# MotherboardThin.net
KiCad netlist of a schematic drawn in EAGLE
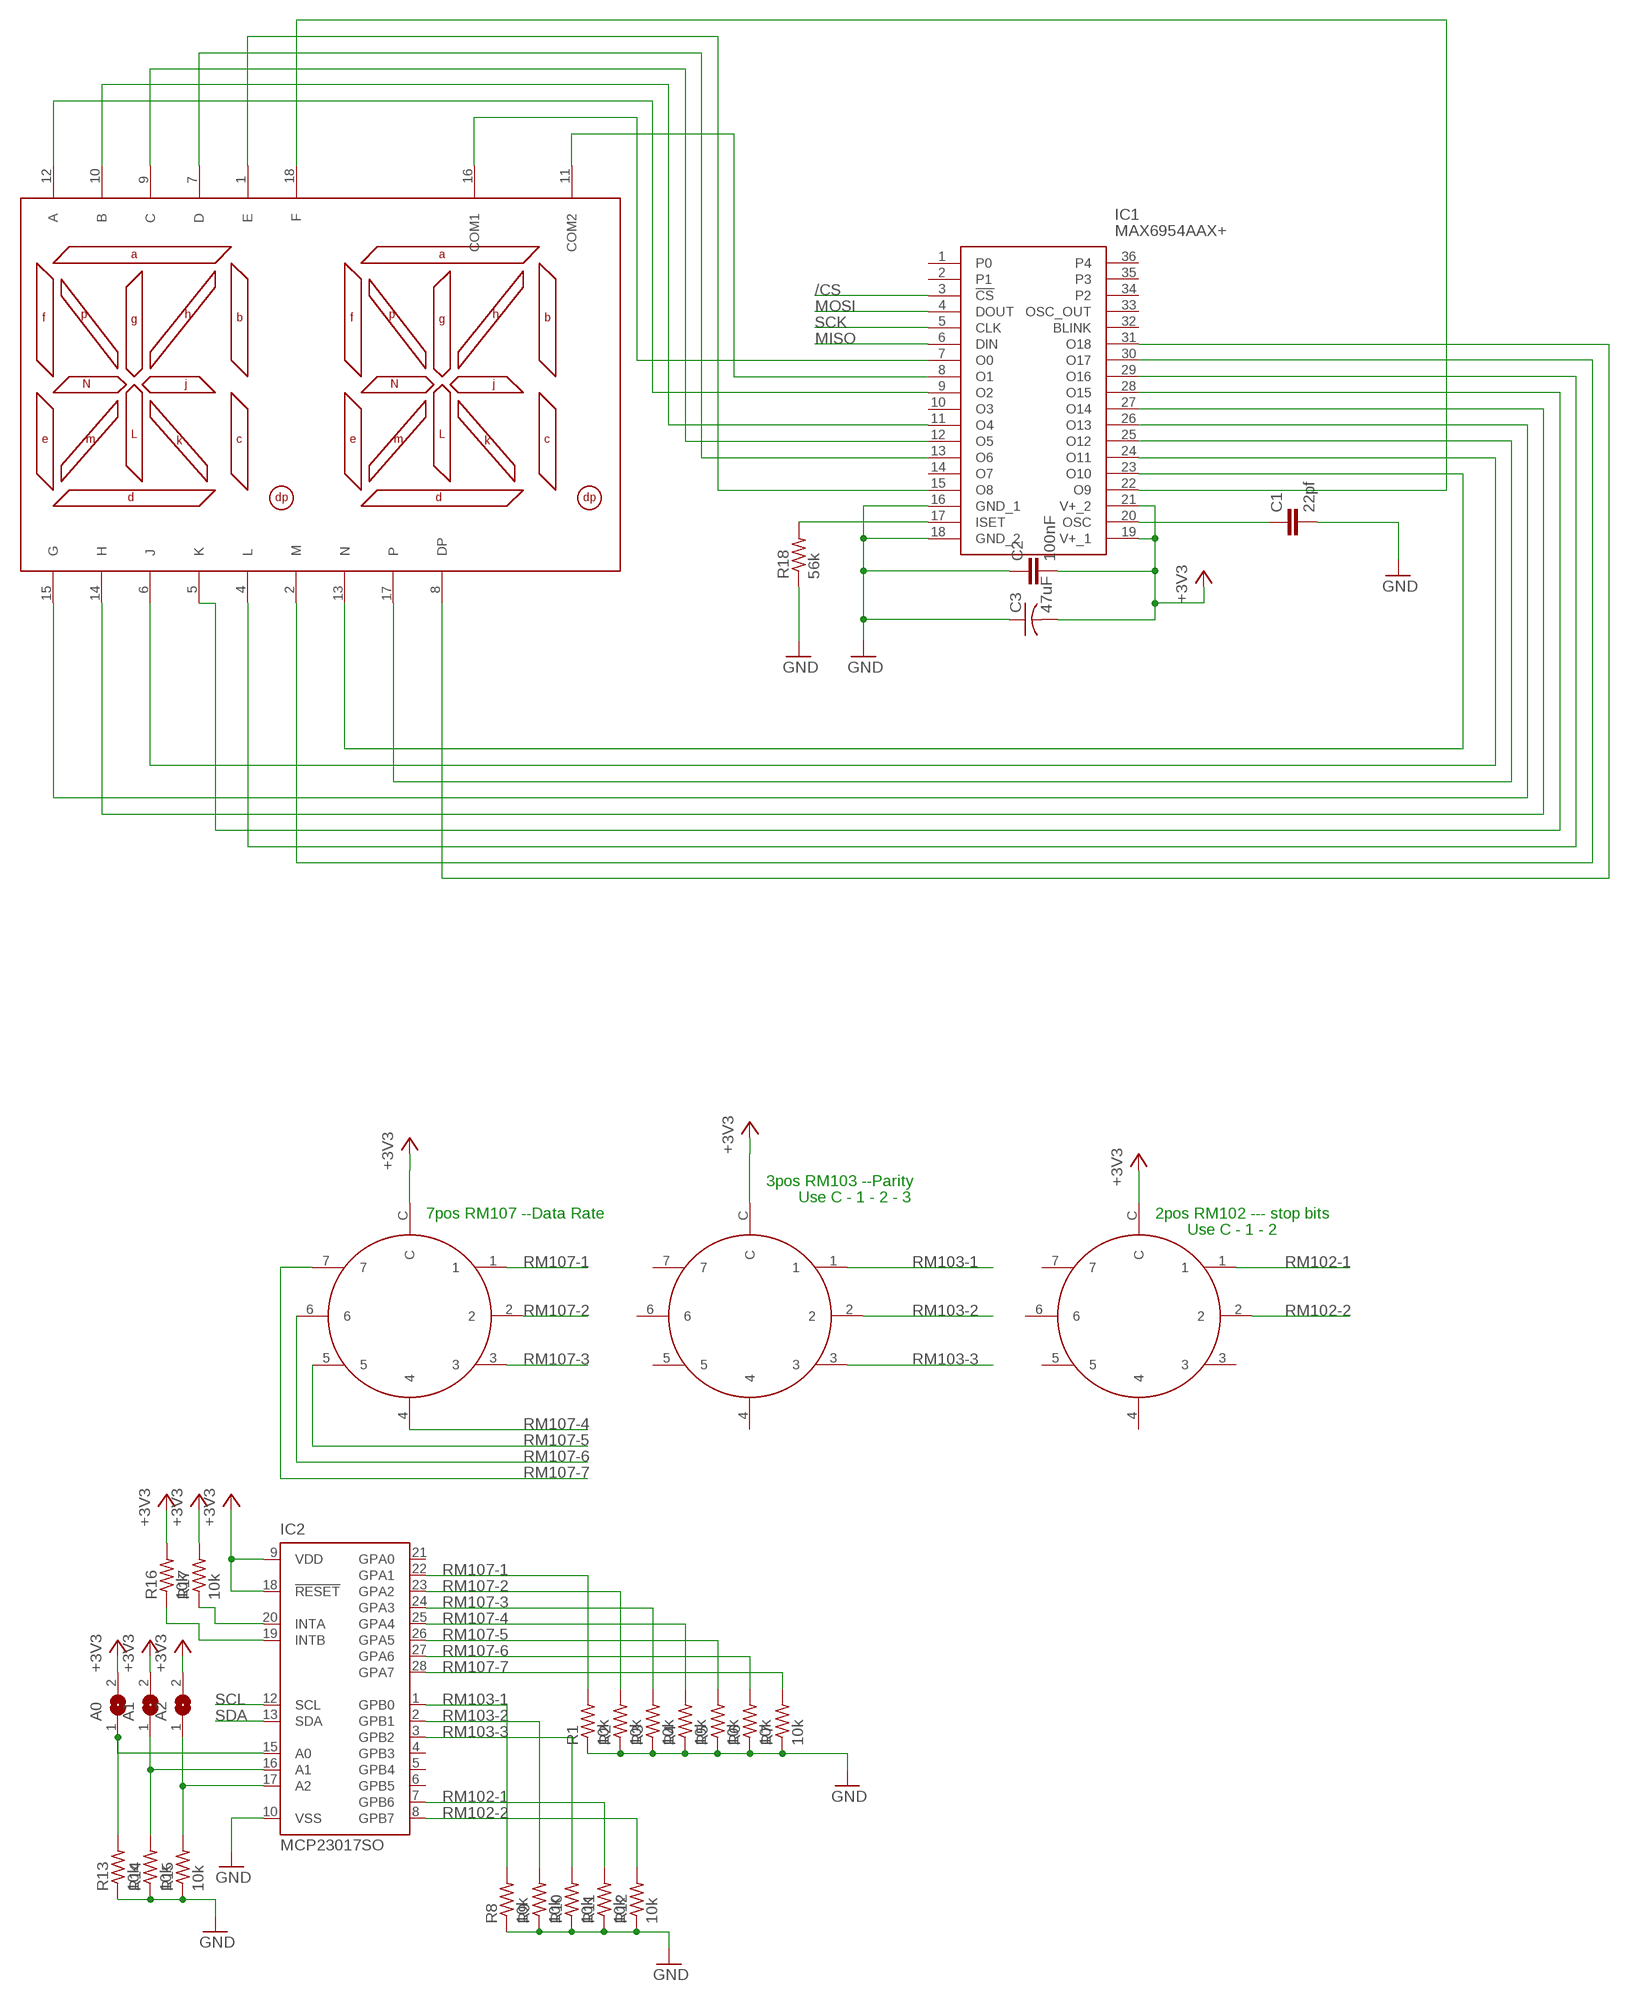
[diagram p0: schematic, sheet 1, part 1 of 2]
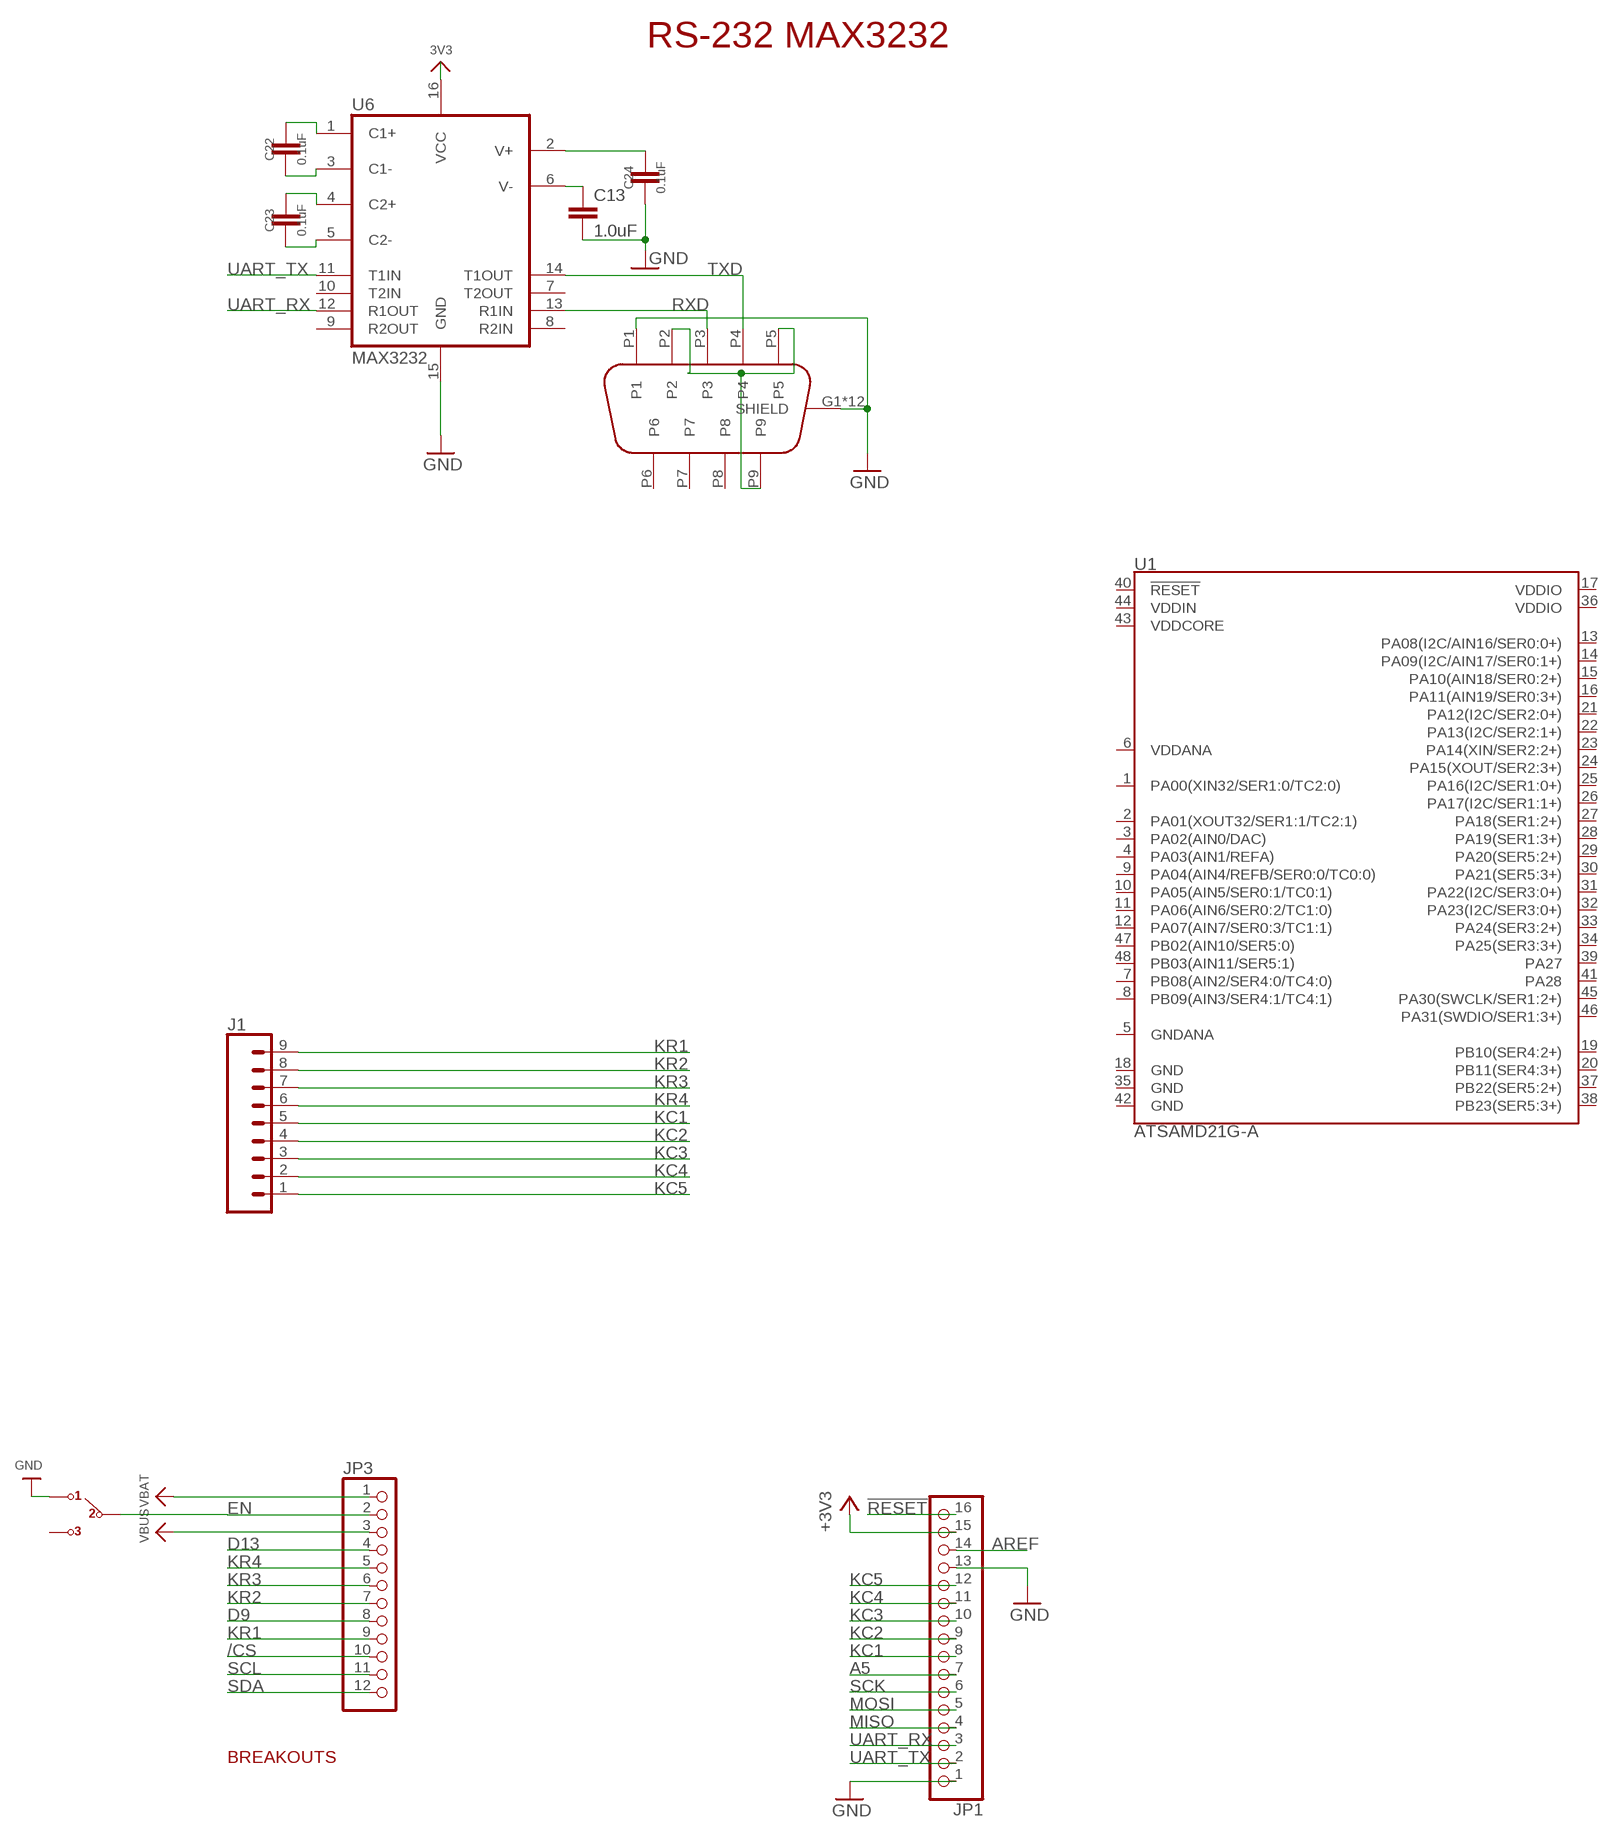
[diagram p1: schematic, sheet 1, part 2 of 2]

(export (version "E")
  (design (tool "Eeschema 10.0.6"))
  (components
    (comp (ref "A0") (value "SJ") (footprint "eagle-import:SJ") (libsource (lib "eagle-import") (part "SJ")))
    (comp (ref "A1") (value "SJ") (footprint "eagle-import:SJ") (libsource (lib "eagle-import") (part "SJ")))
    (comp (ref "A2") (value "SJ") (footprint "eagle-import:SJ") (libsource (lib "eagle-import") (part "SJ")))
    (comp (ref "C1")
      (value "22pf")
      (footprint "eagle-import:0805")
      (libsource (lib "eagle-import") (part "1.0UF-0805-25V-(+80/-20%)"))
    )
    (comp (ref "C2")
      (value "100nF")
      (footprint "eagle-import:0805")
      (libsource (lib "eagle-import") (part "1.0UF-0805-25V-(+80/-20%)"))
    )
    (comp (ref "C3")
      (value "47uF")
      (footprint "eagle-import:C1206")
      (libsource (lib "eagle-import") (part "C-USC1206"))
    )
    (comp (ref "C13")
      (value "1.0uF")
      (footprint "eagle-import:0805")
      (libsource (lib "eagle-import") (part "1.0UF-0805-25V-10%"))
    )
    (comp (ref "C22")
      (value "0.1uF")
      (footprint "eagle-import:0805")
      (libsource (lib "eagle-import") (part "1.0UF-0805-25V-10%"))
    )
    (comp (ref "C23")
      (value "0.1uF")
      (footprint "eagle-import:0805")
      (libsource (lib "eagle-import") (part "1.0UF-0805-25V-10%"))
    )
    (comp (ref "C24")
      (value "0.1uF")
      (footprint "eagle-import:0805")
      (libsource (lib "eagle-import") (part "1.0UF-0805-25V-10%"))
    )
    (comp (ref "DE9FEMALE")
      (value "EDGEMOUNTDE9")
      (footprint "eagle-import:DE09S065TLF")
      (libsource (lib "eagle-import") (part "EDGEMOUNTDE9"))
    )
    (comp (ref "IC1")
      (value "MAX6954AAX+")
      (footprint "eagle-import:SOP80P1030X264-36N")
      (fields (field (name "MOUSER_PART_NUMBER") "700-MAX6954AAX"))
      (libsource (lib "eagle-import") (part "MAX6954AAX+"))
    )
    (comp (ref "IC2")
      (value "MCP23017SO")
      (footprint "eagle-import:SO28W")
      (libsource (lib "eagle-import") (part "MCP23017SO"))
    )
    (comp (ref "J1")
      (value "CONN_09")
      (footprint "eagle-import:1X09")
      (libsource (lib "eagle-import") (part "CONN_09"))
    )
    (comp (ref "JP1")
      (value "HEADER-1X16ROUND")
      (footprint "eagle-import:1X16_ROUND")
      (libsource (lib "eagle-import") (part "HEADER-1X16ROUND"))
    )
    (comp (ref "JP3")
      (value "HEADER-1X12")
      (footprint "eagle-import:1X12_ROUND")
      (libsource (lib "eagle-import") (part "HEADER-1X12"))
    )
    (comp (ref "R1")
      (value "10k")
      (footprint "eagle-import:M0805")
      (libsource (lib "eagle-import") (part "R-US_M0805"))
    )
    (comp (ref "R2")
      (value "10k")
      (footprint "eagle-import:M0805")
      (libsource (lib "eagle-import") (part "R-US_M0805"))
    )
    (comp (ref "R3")
      (value "10k")
      (footprint "eagle-import:M0805")
      (libsource (lib "eagle-import") (part "R-US_M0805"))
    )
    (comp (ref "R4")
      (value "10k")
      (footprint "eagle-import:M0805")
      (libsource (lib "eagle-import") (part "R-US_M0805"))
    )
    (comp (ref "R5")
      (value "10k")
      (footprint "eagle-import:M0805")
      (libsource (lib "eagle-import") (part "R-US_M0805"))
    )
    (comp (ref "R6")
      (value "10k")
      (footprint "eagle-import:M0805")
      (libsource (lib "eagle-import") (part "R-US_M0805"))
    )
    (comp (ref "R7")
      (value "10k")
      (footprint "eagle-import:M0805")
      (libsource (lib "eagle-import") (part "R-US_M0805"))
    )
    (comp (ref "R8")
      (value "10k")
      (footprint "eagle-import:M0805")
      (libsource (lib "eagle-import") (part "R-US_M0805"))
    )
    (comp (ref "R9")
      (value "10k")
      (footprint "eagle-import:M0805")
      (libsource (lib "eagle-import") (part "R-US_M0805"))
    )
    (comp (ref "R10")
      (value "10k")
      (footprint "eagle-import:M0805")
      (libsource (lib "eagle-import") (part "R-US_M0805"))
    )
    (comp (ref "R11")
      (value "10k")
      (footprint "eagle-import:M0805")
      (libsource (lib "eagle-import") (part "R-US_M0805"))
    )
    (comp (ref "R12")
      (value "10k")
      (footprint "eagle-import:M0805")
      (libsource (lib "eagle-import") (part "R-US_M0805"))
    )
    (comp (ref "R13")
      (value "10k")
      (footprint "eagle-import:M0805")
      (libsource (lib "eagle-import") (part "R-US_M0805"))
    )
    (comp (ref "R14")
      (value "10k")
      (footprint "eagle-import:M0805")
      (libsource (lib "eagle-import") (part "R-US_M0805"))
    )
    (comp (ref "R15")
      (value "10k")
      (footprint "eagle-import:M0805")
      (libsource (lib "eagle-import") (part "R-US_M0805"))
    )
    (comp (ref "R16")
      (value "10k")
      (footprint "eagle-import:M0805")
      (libsource (lib "eagle-import") (part "R-US_M0805"))
    )
    (comp (ref "R17")
      (value "10k")
      (footprint "eagle-import:M0805")
      (libsource (lib "eagle-import") (part "R-US_M0805"))
    )
    (comp (ref "R18")
      (value "56k")
      (footprint "eagle-import:M0805")
      (libsource (lib "eagle-import") (part "R-US_M0805"))
    )
    (comp (ref "U$1")
      (value "HDSP-A27C")
      (footprint "eagle-import:DIP-18")
      (libsource (lib "eagle-import") (part "HDSP-A27C"))
    )
    (comp (ref "U$2")
      (value "RM107772BCB")
      (footprint "eagle-import:RM107772BCB")
      (libsource (lib "eagle-import") (part "RM107772BCB"))
    )
    (comp (ref "U$3")
      (value "RM107772BCB")
      (footprint "eagle-import:RM107772BCB")
      (libsource (lib "eagle-import") (part "RM107772BCB"))
    )
    (comp (ref "U$5")
      (value "OS102011MA1QN1")
      (footprint "eagle-import:OS102011MA1QN1")
      (libsource (lib "eagle-import") (part "OS102011MA1QN1"))
    )
    (comp (ref "U$6")
      (value "RM107772BCB")
      (footprint "eagle-import:RM107772BCB")
      (libsource (lib "eagle-import") (part "RM107772BCB"))
    )
    (comp (ref "U1")
      (value "ATSAMD21G-A")
      (footprint "eagle-import:TQFP-48")
      (libsource (lib "eagle-import") (part "ATSAMD21G-A"))
    )
    (comp (ref "U6")
      (value "MAX3232")
      (footprint "eagle-import:SO16")
      (libsource (lib "eagle-import") (part "MAX2323SOIC16"))
    )
  )
  (nets
    (net (code "1") (name "+3V3") (class "Default")
      (node (ref "A0") (pin "2") (pinfunction "2_2") (pintype "passive"))
      (node (ref "A1") (pin "2") (pinfunction "2_2") (pintype "passive"))
      (node (ref "A2") (pin "2") (pinfunction "2_2") (pintype "passive"))
      (node (ref "C2") (pin "2") (pinfunction "2_2") (pintype "passive"))
      (node (ref "C3") (pin "2") (pinfunction "2_2") (pintype "passive"))
      (node (ref "IC1") (pin "19") (pinfunction "V+_1_19") (pintype "bidirectional"))
      (node (ref "IC1") (pin "21") (pinfunction "V+_2_21") (pintype "bidirectional"))
      (node (ref "IC2") (pin "18") (pinfunction "~{RESET}_18") (pintype "input"))
      (node (ref "IC2") (pin "9") (pinfunction "VDD_9") (pintype "power_in"))
      (node (ref "JP1") (pin "15") (pinfunction "15_15") (pintype "passive"))
      (node (ref "R16") (pin "2") (pinfunction "2_2") (pintype "passive"))
      (node (ref "R17") (pin "2") (pinfunction "2_2") (pintype "passive"))
      (node (ref "U$2") (pin "C") (pinfunction "C_C") (pintype "bidirectional"))
      (node (ref "U$3") (pin "C") (pinfunction "C_C") (pintype "bidirectional"))
      (node (ref "U$6") (pin "C") (pinfunction "C_C") (pintype "bidirectional"))
    )
    (net (code "2") (name "/A5") (class "Default")
      (node (ref "JP1") (pin "7") (pinfunction "7_7") (pintype "passive"))
    )
    (net (code "3") (name "/AREF") (class "Default")
      (node (ref "JP1") (pin "14") (pinfunction "14_14") (pintype "passive"))
    )
    (net (code "4") (name "/D9") (class "Default")
      (node (ref "JP3") (pin "8") (pinfunction "8_8") (pintype "passive"))
    )
    (net (code "5") (name "/D13") (class "Default")
      (node (ref "JP3") (pin "4") (pinfunction "4_4") (pintype "passive"))
    )
    (net (code "6") (name "/EN") (class "Default")
      (node (ref "JP3") (pin "2") (pinfunction "2_2") (pintype "passive"))
      (node (ref "U$5") (pin "P$2") (pinfunction "P$2_P$2") (pintype "bidirectional"))
    )
    (net (code "7") (name "/KC1") (class "Default")
      (node (ref "J1") (pin "5") (pinfunction "5_5") (pintype "passive"))
      (node (ref "JP1") (pin "8") (pinfunction "8_8") (pintype "passive"))
    )
    (net (code "8") (name "/KC2") (class "Default")
      (node (ref "J1") (pin "4") (pinfunction "4_4") (pintype "passive"))
      (node (ref "JP1") (pin "9") (pinfunction "9_9") (pintype "passive"))
    )
    (net (code "9") (name "/KC3") (class "Default")
      (node (ref "J1") (pin "3") (pinfunction "3_3") (pintype "passive"))
      (node (ref "JP1") (pin "10") (pinfunction "10_10") (pintype "passive"))
    )
    (net (code "10") (name "/KC4") (class "Default")
      (node (ref "J1") (pin "2") (pinfunction "2_2") (pintype "passive"))
      (node (ref "JP1") (pin "11") (pinfunction "11_11") (pintype "passive"))
    )
    (net (code "11") (name "/KC5") (class "Default")
      (node (ref "J1") (pin "1") (pinfunction "1_1") (pintype "passive"))
      (node (ref "JP1") (pin "12") (pinfunction "12_12") (pintype "passive"))
    )
    (net (code "12") (name "/KR1") (class "Default")
      (node (ref "J1") (pin "9") (pinfunction "9_9") (pintype "passive"))
      (node (ref "JP3") (pin "9") (pinfunction "9_9") (pintype "passive"))
    )
    (net (code "13") (name "/KR2") (class "Default")
      (node (ref "J1") (pin "8") (pinfunction "8_8") (pintype "passive"))
      (node (ref "JP3") (pin "7") (pinfunction "7_7") (pintype "passive"))
    )
    (net (code "14") (name "/KR3") (class "Default")
      (node (ref "J1") (pin "7") (pinfunction "7_7") (pintype "passive"))
      (node (ref "JP3") (pin "6") (pinfunction "6_6") (pintype "passive"))
    )
    (net (code "15") (name "/KR4") (class "Default")
      (node (ref "J1") (pin "6") (pinfunction "6_6") (pintype "passive"))
      (node (ref "JP3") (pin "5") (pinfunction "5_5") (pintype "passive"))
    )
    (net (code "16") (name "/MISO") (class "Default")
      (node (ref "IC1") (pin "6") (pinfunction "DIN_6") (pintype "input"))
      (node (ref "JP1") (pin "4") (pinfunction "4_4") (pintype "passive"))
    )
    (net (code "17") (name "/MOSI") (class "Default")
      (node (ref "IC1") (pin "4") (pinfunction "DOUT_4") (pintype "output"))
      (node (ref "JP1") (pin "5") (pinfunction "5_5") (pintype "passive"))
    )
    (net (code "18") (name "/RM102-1") (class "Default")
      (node (ref "IC2") (pin "7") (pinfunction "GPB6_7") (pintype "bidirectional"))
      (node (ref "R11") (pin "2") (pinfunction "2_2") (pintype "passive"))
      (node (ref "U$6") (pin "1") (pinfunction "1_1") (pintype "bidirectional"))
    )
    (net (code "19") (name "/RM102-2") (class "Default")
      (node (ref "IC2") (pin "8") (pinfunction "GPB7_8") (pintype "bidirectional"))
      (node (ref "R12") (pin "2") (pinfunction "2_2") (pintype "passive"))
      (node (ref "U$6") (pin "2") (pinfunction "2_2") (pintype "bidirectional"))
    )
    (net (code "20") (name "/RM103-1") (class "Default")
      (node (ref "IC2") (pin "1") (pinfunction "GPB0_1") (pintype "bidirectional"))
      (node (ref "R8") (pin "2") (pinfunction "2_2") (pintype "passive"))
      (node (ref "U$3") (pin "1") (pinfunction "1_1") (pintype "bidirectional"))
    )
    (net (code "21") (name "/RM103-2") (class "Default")
      (node (ref "IC2") (pin "2") (pinfunction "GPB1_2") (pintype "bidirectional"))
      (node (ref "R9") (pin "2") (pinfunction "2_2") (pintype "passive"))
      (node (ref "U$3") (pin "2") (pinfunction "2_2") (pintype "bidirectional"))
    )
    (net (code "22") (name "/RM103-3") (class "Default")
      (node (ref "IC2") (pin "3") (pinfunction "GPB2_3") (pintype "bidirectional"))
      (node (ref "R10") (pin "2") (pinfunction "2_2") (pintype "passive"))
      (node (ref "U$3") (pin "3") (pinfunction "3_3") (pintype "bidirectional"))
    )
    (net (code "23") (name "/RM107-1") (class "Default")
      (node (ref "IC2") (pin "22") (pinfunction "GPA1_22") (pintype "bidirectional"))
      (node (ref "R1") (pin "2") (pinfunction "2_2") (pintype "passive"))
      (node (ref "U$2") (pin "1") (pinfunction "1_1") (pintype "bidirectional"))
    )
    (net (code "24") (name "/RM107-2") (class "Default")
      (node (ref "IC2") (pin "23") (pinfunction "GPA2_23") (pintype "bidirectional"))
      (node (ref "R2") (pin "2") (pinfunction "2_2") (pintype "passive"))
      (node (ref "U$2") (pin "2") (pinfunction "2_2") (pintype "bidirectional"))
    )
    (net (code "25") (name "/RM107-3") (class "Default")
      (node (ref "IC2") (pin "24") (pinfunction "GPA3_24") (pintype "bidirectional"))
      (node (ref "R3") (pin "2") (pinfunction "2_2") (pintype "passive"))
      (node (ref "U$2") (pin "3") (pinfunction "3_3") (pintype "bidirectional"))
    )
    (net (code "26") (name "/RM107-4") (class "Default")
      (node (ref "IC2") (pin "25") (pinfunction "GPA4_25") (pintype "bidirectional"))
      (node (ref "R4") (pin "2") (pinfunction "2_2") (pintype "passive"))
      (node (ref "U$2") (pin "4") (pinfunction "4_4") (pintype "bidirectional"))
    )
    (net (code "27") (name "/RM107-5") (class "Default")
      (node (ref "IC2") (pin "26") (pinfunction "GPA5_26") (pintype "bidirectional"))
      (node (ref "R5") (pin "2") (pinfunction "2_2") (pintype "passive"))
      (node (ref "U$2") (pin "5") (pinfunction "5_5") (pintype "bidirectional"))
    )
    (net (code "28") (name "/RM107-6") (class "Default")
      (node (ref "IC2") (pin "27") (pinfunction "GPA6_27") (pintype "bidirectional"))
      (node (ref "R6") (pin "2") (pinfunction "2_2") (pintype "passive"))
      (node (ref "U$2") (pin "6") (pinfunction "6_6") (pintype "bidirectional"))
    )
    (net (code "29") (name "/RM107-7") (class "Default")
      (node (ref "IC2") (pin "28") (pinfunction "GPA7_28") (pintype "bidirectional"))
      (node (ref "R7") (pin "2") (pinfunction "2_2") (pintype "passive"))
      (node (ref "U$2") (pin "7") (pinfunction "7_7") (pintype "bidirectional"))
    )
    (net (code "30") (name "/RXD") (class "Default")
      (node (ref "DE9FEMALE") (pin "P3") (pinfunction "P3_P3") (pintype "bidirectional"))
      (node (ref "U6") (pin "13") (pinfunction "R1IN_13") (pintype "input"))
    )
    (net (code "31") (name "/SCK") (class "Default")
      (node (ref "IC1") (pin "5") (pinfunction "CLK_5") (pintype "input"))
      (node (ref "JP1") (pin "6") (pinfunction "6_6") (pintype "passive"))
    )
    (net (code "32") (name "/SCL") (class "Default")
      (node (ref "IC2") (pin "12") (pinfunction "SCL_12") (pintype "input"))
      (node (ref "JP3") (pin "11") (pinfunction "11_11") (pintype "passive"))
    )
    (net (code "33") (name "/SDA") (class "Default")
      (node (ref "IC2") (pin "13") (pinfunction "SDA_13") (pintype "bidirectional"))
      (node (ref "JP3") (pin "12") (pinfunction "12_12") (pintype "passive"))
    )
    (net (code "34") (name "/TXD") (class "Default")
      (node (ref "DE9FEMALE") (pin "P4") (pinfunction "P4_P4") (pintype "bidirectional"))
      (node (ref "U6") (pin "14") (pinfunction "T1OUT_14") (pintype "output"))
    )
    (net (code "35") (name "/UART_RX") (class "Default")
      (node (ref "JP1") (pin "3") (pinfunction "3_3") (pintype "passive"))
      (node (ref "U6") (pin "12") (pinfunction "R1OUT_12") (pintype "output"))
    )
    (net (code "36") (name "/UART_TX") (class "Default")
      (node (ref "JP1") (pin "2") (pinfunction "2_2") (pintype "passive"))
      (node (ref "U6") (pin "11") (pinfunction "T1IN_11") (pintype "input"))
    )
    (net (code "37") (name "/{slash}CS") (class "Default")
      (node (ref "IC1") (pin "3") (pinfunction "~{CS}_3") (pintype "input"))
      (node (ref "JP3") (pin "10") (pinfunction "10_10") (pintype "passive"))
    )
    (net (code "38") (name "/~{RESET}") (class "Default")
      (node (ref "JP1") (pin "16") (pinfunction "16_16") (pintype "passive"))
    )
    (net (code "39") (name "3V3") (class "Default")
      (node (ref "U6") (pin "16") (pinfunction "VCC_16") (pintype "bidirectional"))
    )
    (net (code "40") (name "GND") (class "Default")
      (node (ref "C1") (pin "2") (pinfunction "2_2") (pintype "passive"))
      (node (ref "C13") (pin "2") (pinfunction "2_2") (pintype "passive"))
      (node (ref "C2") (pin "1") (pinfunction "1_1") (pintype "passive"))
      (node (ref "C24") (pin "2") (pinfunction "2_2") (pintype "passive"))
      (node (ref "C3") (pin "1") (pinfunction "1_1") (pintype "passive"))
      (node (ref "DE9FEMALE") (pin "G1") (pinfunction "SHIELD_G1") (pintype "bidirectional"))
      (node (ref "DE9FEMALE") (pin "G10") (pinfunction "SHIELD_G10") (pintype "bidirectional"))
      (node (ref "DE9FEMALE") (pin "G11") (pinfunction "SHIELD_G11") (pintype "bidirectional"))
      (node (ref "DE9FEMALE") (pin "G12") (pinfunction "SHIELD_G12") (pintype "bidirectional"))
      (node (ref "DE9FEMALE") (pin "G2") (pinfunction "SHIELD_G2") (pintype "bidirectional"))
      (node (ref "DE9FEMALE") (pin "G3") (pinfunction "SHIELD_G3") (pintype "bidirectional"))
      (node (ref "DE9FEMALE") (pin "G4") (pinfunction "SHIELD_G4") (pintype "bidirectional"))
      (node (ref "DE9FEMALE") (pin "G5") (pinfunction "SHIELD_G5") (pintype "bidirectional"))
      (node (ref "DE9FEMALE") (pin "G6") (pinfunction "SHIELD_G6") (pintype "bidirectional"))
      (node (ref "DE9FEMALE") (pin "G7") (pinfunction "SHIELD_G7") (pintype "bidirectional"))
      (node (ref "DE9FEMALE") (pin "G8") (pinfunction "SHIELD_G8") (pintype "bidirectional"))
      (node (ref "DE9FEMALE") (pin "G9") (pinfunction "SHIELD_G9") (pintype "bidirectional"))
      (node (ref "DE9FEMALE") (pin "P1") (pinfunction "P1_P1") (pintype "bidirectional"))
      (node (ref "IC1") (pin "16") (pinfunction "GND_1_16") (pintype "power_in"))
      (node (ref "IC1") (pin "18") (pinfunction "GND_2_18") (pintype "power_in"))
      (node (ref "IC2") (pin "10") (pinfunction "VSS_10") (pintype "power_in"))
      (node (ref "JP1") (pin "1") (pinfunction "1_1") (pintype "passive"))
      (node (ref "JP1") (pin "13") (pinfunction "13_13") (pintype "passive"))
      (node (ref "R1") (pin "1") (pinfunction "1_1") (pintype "passive"))
      (node (ref "R10") (pin "1") (pinfunction "1_1") (pintype "passive"))
      (node (ref "R11") (pin "1") (pinfunction "1_1") (pintype "passive"))
      (node (ref "R12") (pin "1") (pinfunction "1_1") (pintype "passive"))
      (node (ref "R13") (pin "1") (pinfunction "1_1") (pintype "passive"))
      (node (ref "R14") (pin "1") (pinfunction "1_1") (pintype "passive"))
      (node (ref "R15") (pin "1") (pinfunction "1_1") (pintype "passive"))
      (node (ref "R18") (pin "1") (pinfunction "1_1") (pintype "passive"))
      (node (ref "R2") (pin "1") (pinfunction "1_1") (pintype "passive"))
      (node (ref "R3") (pin "1") (pinfunction "1_1") (pintype "passive"))
      (node (ref "R4") (pin "1") (pinfunction "1_1") (pintype "passive"))
      (node (ref "R5") (pin "1") (pinfunction "1_1") (pintype "passive"))
      (node (ref "R6") (pin "1") (pinfunction "1_1") (pintype "passive"))
      (node (ref "R7") (pin "1") (pinfunction "1_1") (pintype "passive"))
      (node (ref "R8") (pin "1") (pinfunction "1_1") (pintype "passive"))
      (node (ref "R9") (pin "1") (pinfunction "1_1") (pintype "passive"))
      (node (ref "U$5") (pin "P$1") (pinfunction "P$1_P$1") (pintype "bidirectional"))
      (node (ref "U6") (pin "15") (pinfunction "GND_15") (pintype "bidirectional"))
    )
    (net (code "41") (name "Net-(DE9FEMALE-PadP2)") (class "Default")
      (node (ref "DE9FEMALE") (pin "P2") (pinfunction "P2_P2") (pintype "bidirectional"))
      (node (ref "DE9FEMALE") (pin "P5") (pinfunction "P5_P5") (pintype "bidirectional"))
      (node (ref "DE9FEMALE") (pin "P9") (pinfunction "P9_P9") (pintype "bidirectional"))
    )
    (net (code "42") (name "Net-(IC1-ISET)") (class "Default")
      (node (ref "IC1") (pin "17") (pinfunction "ISET_17") (pintype "bidirectional"))
      (node (ref "R18") (pin "2") (pinfunction "2_2") (pintype "passive"))
    )
    (net (code "43") (name "Net-(IC1-O0)") (class "Default")
      (node (ref "IC1") (pin "7") (pinfunction "O0_7") (pintype "output"))
      (node (ref "U$1") (pin "16") (pinfunction "COM1_16") (pintype "bidirectional"))
    )
    (net (code "44") (name "Net-(IC1-O1)") (class "Default")
      (node (ref "IC1") (pin "8") (pinfunction "O1_8") (pintype "output"))
      (node (ref "U$1") (pin "11") (pinfunction "COM2_11") (pintype "bidirectional"))
    )
    (net (code "45") (name "Net-(IC1-O2)") (class "Default")
      (node (ref "IC1") (pin "9") (pinfunction "O2_9") (pintype "output"))
      (node (ref "U$1") (pin "12") (pinfunction "A_12") (pintype "bidirectional"))
    )
    (net (code "46") (name "Net-(IC1-O4)") (class "Default")
      (node (ref "IC1") (pin "11") (pinfunction "O4_11") (pintype "output"))
      (node (ref "U$1") (pin "10") (pinfunction "B_10") (pintype "bidirectional"))
    )
    (net (code "47") (name "Net-(IC1-O5)") (class "Default")
      (node (ref "IC1") (pin "12") (pinfunction "O5_12") (pintype "output"))
      (node (ref "U$1") (pin "9") (pinfunction "C_9") (pintype "bidirectional"))
    )
    (net (code "48") (name "Net-(IC1-O6)") (class "Default")
      (node (ref "IC1") (pin "13") (pinfunction "O6_13") (pintype "output"))
      (node (ref "U$1") (pin "7") (pinfunction "D_7") (pintype "bidirectional"))
    )
    (net (code "49") (name "Net-(IC1-O8)") (class "Default")
      (node (ref "IC1") (pin "15") (pinfunction "O8_15") (pintype "output"))
      (node (ref "U$1") (pin "1") (pinfunction "E_1") (pintype "bidirectional"))
    )
    (net (code "50") (name "Net-(IC1-O9)") (class "Default")
      (node (ref "IC1") (pin "22") (pinfunction "O9_22") (pintype "bidirectional"))
      (node (ref "U$1") (pin "18") (pinfunction "F_18") (pintype "bidirectional"))
    )
    (net (code "51") (name "Net-(IC1-O10)") (class "Default")
      (node (ref "IC1") (pin "23") (pinfunction "O10_23") (pintype "bidirectional"))
      (node (ref "U$1") (pin "13") (pinfunction "N_13") (pintype "bidirectional"))
    )
    (net (code "52") (name "Net-(IC1-O11)") (class "Default")
      (node (ref "IC1") (pin "24") (pinfunction "O11_24") (pintype "bidirectional"))
      (node (ref "U$1") (pin "6") (pinfunction "J_6") (pintype "bidirectional"))
    )
    (net (code "53") (name "Net-(IC1-O12)") (class "Default")
      (node (ref "IC1") (pin "25") (pinfunction "O12_25") (pintype "bidirectional"))
      (node (ref "U$1") (pin "17") (pinfunction "P_17") (pintype "bidirectional"))
    )
    (net (code "54") (name "Net-(IC1-O13)") (class "Default")
      (node (ref "IC1") (pin "26") (pinfunction "O13_26") (pintype "bidirectional"))
      (node (ref "U$1") (pin "15") (pinfunction "G_15") (pintype "bidirectional"))
    )
    (net (code "55") (name "Net-(IC1-O14)") (class "Default")
      (node (ref "IC1") (pin "27") (pinfunction "O14_27") (pintype "bidirectional"))
      (node (ref "U$1") (pin "14") (pinfunction "H_14") (pintype "bidirectional"))
    )
    (net (code "56") (name "Net-(IC1-O15)") (class "Default")
      (node (ref "IC1") (pin "28") (pinfunction "O15_28") (pintype "bidirectional"))
      (node (ref "U$1") (pin "5") (pinfunction "K_5") (pintype "bidirectional"))
    )
    (net (code "57") (name "Net-(IC1-O16)") (class "Default")
      (node (ref "IC1") (pin "29") (pinfunction "O16_29") (pintype "bidirectional"))
      (node (ref "U$1") (pin "4") (pinfunction "L_4") (pintype "bidirectional"))
    )
    (net (code "58") (name "Net-(IC1-O17)") (class "Default")
      (node (ref "IC1") (pin "30") (pinfunction "O17_30") (pintype "bidirectional"))
      (node (ref "U$1") (pin "2") (pinfunction "M_2") (pintype "bidirectional"))
    )
    (net (code "59") (name "Net-(IC1-O18)") (class "Default")
      (node (ref "IC1") (pin "31") (pinfunction "O18_31") (pintype "bidirectional"))
      (node (ref "U$1") (pin "8") (pinfunction "DP_8") (pintype "bidirectional"))
    )
    (net (code "60") (name "Net-(IC1-OSC)") (class "Default")
      (node (ref "C1") (pin "1") (pinfunction "1_1") (pintype "passive"))
      (node (ref "IC1") (pin "20") (pinfunction "OSC_20") (pintype "bidirectional"))
    )
    (net (code "61") (name "Net-(IC2-A0)") (class "Default")
      (node (ref "A0") (pin "1") (pinfunction "1_1") (pintype "passive"))
      (node (ref "IC2") (pin "15") (pinfunction "A0_15") (pintype "input"))
      (node (ref "R13") (pin "2") (pinfunction "2_2") (pintype "passive"))
    )
    (net (code "62") (name "Net-(IC2-A1)") (class "Default")
      (node (ref "A1") (pin "1") (pinfunction "1_1") (pintype "passive"))
      (node (ref "IC2") (pin "16") (pinfunction "A1_16") (pintype "input"))
      (node (ref "R14") (pin "2") (pinfunction "2_2") (pintype "passive"))
    )
    (net (code "63") (name "Net-(IC2-A2)") (class "Default")
      (node (ref "A2") (pin "1") (pinfunction "1_1") (pintype "passive"))
      (node (ref "IC2") (pin "17") (pinfunction "A2_17") (pintype "input"))
      (node (ref "R15") (pin "2") (pinfunction "2_2") (pintype "passive"))
    )
    (net (code "64") (name "Net-(IC2-INTA)") (class "Default")
      (node (ref "IC2") (pin "20") (pinfunction "INTA_20") (pintype "output"))
      (node (ref "R17") (pin "1") (pinfunction "1_1") (pintype "passive"))
    )
    (net (code "65") (name "Net-(IC2-INTB)") (class "Default")
      (node (ref "IC2") (pin "19") (pinfunction "INTB_19") (pintype "output"))
      (node (ref "R16") (pin "1") (pinfunction "1_1") (pintype "passive"))
    )
    (net (code "66") (name "Net-(U6-C1+)") (class "Default")
      (node (ref "C22") (pin "1") (pinfunction "1_1") (pintype "passive"))
      (node (ref "U6") (pin "1") (pinfunction "C1+_1") (pintype "bidirectional"))
    )
    (net (code "67") (name "Net-(U6-C1-)") (class "Default")
      (node (ref "C22") (pin "2") (pinfunction "2_2") (pintype "passive"))
      (node (ref "U6") (pin "3") (pinfunction "C1-_3") (pintype "bidirectional"))
    )
    (net (code "68") (name "Net-(U6-C2+)") (class "Default")
      (node (ref "C23") (pin "1") (pinfunction "1_1") (pintype "passive"))
      (node (ref "U6") (pin "4") (pinfunction "C2+_4") (pintype "bidirectional"))
    )
    (net (code "69") (name "Net-(U6-C2-)") (class "Default")
      (node (ref "C23") (pin "2") (pinfunction "2_2") (pintype "passive"))
      (node (ref "U6") (pin "5") (pinfunction "C2-_5") (pintype "bidirectional"))
    )
    (net (code "70") (name "Net-(U6-V+)") (class "Default")
      (node (ref "C24") (pin "1") (pinfunction "1_1") (pintype "passive"))
      (node (ref "U6") (pin "2") (pinfunction "V+_2") (pintype "bidirectional"))
    )
    (net (code "71") (name "Net-(U6-V-)") (class "Default")
      (node (ref "C13") (pin "1") (pinfunction "1_1") (pintype "passive"))
      (node (ref "U6") (pin "6") (pinfunction "V-_6") (pintype "bidirectional"))
    )
    (net (code "72") (name "VBAT") (class "Default")
      (node (ref "JP3") (pin "1") (pinfunction "1_1") (pintype "passive"))
    )
    (net (code "73") (name "VBUS") (class "Default")
      (node (ref "JP3") (pin "3") (pinfunction "3_3") (pintype "passive"))
    )
    (net (code "74") (name "unconnected-(DE9FEMALE-PadP6)") (class "Default")
      (node (ref "DE9FEMALE") (pin "P6") (pinfunction "P6_P6") (pintype "bidirectional"))
    )
    (net (code "75") (name "unconnected-(DE9FEMALE-PadP7)") (class "Default")
      (node (ref "DE9FEMALE") (pin "P7") (pinfunction "P7_P7") (pintype "bidirectional"))
    )
    (net (code "76") (name "unconnected-(DE9FEMALE-PadP8)") (class "Default")
      (node (ref "DE9FEMALE") (pin "P8") (pinfunction "P8_P8") (pintype "bidirectional"))
    )
    (net (code "77") (name "unconnected-(IC1-BLINK-Pad32)") (class "Default")
      (node (ref "IC1") (pin "32") (pinfunction "BLINK_32") (pintype "input"))
    )
    (net (code "78") (name "unconnected-(IC1-O3-Pad10)") (class "Default")
      (node (ref "IC1") (pin "10") (pinfunction "O3_10") (pintype "output"))
    )
    (net (code "79") (name "unconnected-(IC1-O7-Pad14)") (class "Default")
      (node (ref "IC1") (pin "14") (pinfunction "O7_14") (pintype "output"))
    )
    (net (code "80") (name "unconnected-(IC1-OSC_OUT-Pad33)") (class "Default")
      (node (ref "IC1") (pin "33") (pinfunction "OSC_OUT_33") (pintype "output"))
    )
    (net (code "81") (name "unconnected-(IC1-P0-Pad1)") (class "Default")
      (node (ref "IC1") (pin "1") (pinfunction "P0_1") (pintype "bidirectional"))
    )
    (net (code "82") (name "unconnected-(IC1-P1-Pad2)") (class "Default")
      (node (ref "IC1") (pin "2") (pinfunction "P1_2") (pintype "bidirectional"))
    )
    (net (code "83") (name "unconnected-(IC1-P2-Pad34)") (class "Default")
      (node (ref "IC1") (pin "34") (pinfunction "P2_34") (pintype "bidirectional"))
    )
    (net (code "84") (name "unconnected-(IC1-P3-Pad35)") (class "Default")
      (node (ref "IC1") (pin "35") (pinfunction "P3_35") (pintype "bidirectional"))
    )
    (net (code "85") (name "unconnected-(IC1-P4-Pad36)") (class "Default")
      (node (ref "IC1") (pin "36") (pinfunction "P4_36") (pintype "bidirectional"))
    )
    (net (code "86") (name "unconnected-(IC2-GPA0-Pad21)") (class "Default")
      (node (ref "IC2") (pin "21") (pinfunction "GPA0_21") (pintype "bidirectional"))
    )
    (net (code "87") (name "unconnected-(IC2-GPB3-Pad4)") (class "Default")
      (node (ref "IC2") (pin "4") (pinfunction "GPB3_4") (pintype "bidirectional"))
    )
    (net (code "88") (name "unconnected-(IC2-GPB4-Pad5)") (class "Default")
      (node (ref "IC2") (pin "5") (pinfunction "GPB4_5") (pintype "bidirectional"))
    )
    (net (code "89") (name "unconnected-(IC2-GPB5-Pad6)") (class "Default")
      (node (ref "IC2") (pin "6") (pinfunction "GPB5_6") (pintype "bidirectional"))
    )
    (net (code "90") (name "unconnected-(U$3-Pad4)") (class "Default")
      (node (ref "U$3") (pin "4") (pinfunction "4_4") (pintype "bidirectional"))
    )
    (net (code "91") (name "unconnected-(U$3-Pad5)") (class "Default")
      (node (ref "U$3") (pin "5") (pinfunction "5_5") (pintype "bidirectional"))
    )
    (net (code "92") (name "unconnected-(U$3-Pad6)") (class "Default")
      (node (ref "U$3") (pin "6") (pinfunction "6_6") (pintype "bidirectional"))
    )
    (net (code "93") (name "unconnected-(U$3-Pad7)") (class "Default")
      (node (ref "U$3") (pin "7") (pinfunction "7_7") (pintype "bidirectional"))
    )
    (net (code "94") (name "unconnected-(U$5-CASE-PadCASE1)") (class "Default")
      (node (ref "U$5") (pin "CASE1") (pinfunction "CASE_CASE1") (pintype "no_connect"))
    )
    (net (code "95") (name "unconnected-(U$5-CASE-PadCASE2)") (class "Default")
      (node (ref "U$5") (pin "CASE2") (pinfunction "CASE_CASE2") (pintype "no_connect"))
    )
    (net (code "96") (name "unconnected-(U$5-PadP$3)") (class "Default")
      (node (ref "U$5") (pin "P$3") (pinfunction "P$3_P$3") (pintype "bidirectional"))
    )
    (net (code "97") (name "unconnected-(U$6-Pad3)") (class "Default")
      (node (ref "U$6") (pin "3") (pinfunction "3_3") (pintype "bidirectional"))
    )
    (net (code "98") (name "unconnected-(U$6-Pad4)") (class "Default")
      (node (ref "U$6") (pin "4") (pinfunction "4_4") (pintype "bidirectional"))
    )
    (net (code "99") (name "unconnected-(U$6-Pad5)") (class "Default")
      (node (ref "U$6") (pin "5") (pinfunction "5_5") (pintype "bidirectional"))
    )
    (net (code "100") (name "unconnected-(U$6-Pad6)") (class "Default")
      (node (ref "U$6") (pin "6") (pinfunction "6_6") (pintype "bidirectional"))
    )
    (net (code "101") (name "unconnected-(U$6-Pad7)") (class "Default")
      (node (ref "U$6") (pin "7") (pinfunction "7_7") (pintype "bidirectional"))
    )
    (net (code "102") (name "unconnected-(U1-GND-Pad18)") (class "Default")
      (node (ref "U1") (pin "18") (pinfunction "GND_18") (pintype "bidirectional"))
    )
    (net (code "103") (name "unconnected-(U1-GND-Pad35)") (class "Default")
      (node (ref "U1") (pin "35") (pinfunction "GND_35") (pintype "bidirectional"))
    )
    (net (code "104") (name "unconnected-(U1-GND-Pad42)") (class "Default")
      (node (ref "U1") (pin "42") (pinfunction "GND_42") (pintype "bidirectional"))
    )
    (net (code "105") (name "unconnected-(U1-GNDANA-Pad5)") (class "Default")
      (node (ref "U1") (pin "5") (pinfunction "GNDANA_5") (pintype "bidirectional"))
    )
    (net (code "106") (name "unconnected-(U1-PA00(XIN32{slash}SER1:0{slash}TC2:0)-Pad1)") (class "Default")
      (node (ref "U1") (pin "1") (pinfunction "PA00(XIN32/SER1:0/TC2:0)_1") (pintype "bidirectional"))
    )
    (net (code "107") (name "unconnected-(U1-PA01(XOUT32{slash}SER1:1{slash}TC2:1)-Pad2)") (class "Default")
      (node (ref "U1") (pin "2") (pinfunction "PA01(XOUT32/SER1:1/TC2:1)_2") (pintype "bidirectional"))
    )
    (net (code "108") (name "unconnected-(U1-PA02(AIN0{slash}DAC)-Pad3)") (class "Default")
      (node (ref "U1") (pin "3") (pinfunction "PA02(AIN0/DAC)_3") (pintype "bidirectional"))
    )
    (net (code "109") (name "unconnected-(U1-PA03(AIN1{slash}REFA)-Pad4)") (class "Default")
      (node (ref "U1") (pin "4") (pinfunction "PA03(AIN1/REFA)_4") (pintype "bidirectional"))
    )
    (net (code "110") (name "unconnected-(U1-PA04(AIN4{slash}REFB{slash}SER0:0{slash}TC0:0)-Pad9)") (class "Default")
      (node (ref "U1") (pin "9") (pinfunction "PA04(AIN4/REFB/SER0:0/TC0:0)_9") (pintype "bidirectional"))
    )
    (net (code "111") (name "unconnected-(U1-PA05(AIN5{slash}SER0:1{slash}TC0:1)-Pad10)") (class "Default")
      (node (ref "U1") (pin "10") (pinfunction "PA05(AIN5/SER0:1/TC0:1)_10") (pintype "bidirectional"))
    )
    (net (code "112") (name "unconnected-(U1-PA06(AIN6{slash}SER0:2{slash}TC1:0)-Pad11)") (class "Default")
      (node (ref "U1") (pin "11") (pinfunction "PA06(AIN6/SER0:2/TC1:0)_11") (pintype "bidirectional"))
    )
    (net (code "113") (name "unconnected-(U1-PA07(AIN7{slash}SER0:3{slash}TC1:1)-Pad12)") (class "Default")
      (node (ref "U1") (pin "12") (pinfunction "PA07(AIN7/SER0:3/TC1:1)_12") (pintype "bidirectional"))
    )
    (net (code "114") (name "unconnected-(U1-PA08(I2C{slash}AIN16{slash}SER0:0+)-Pad13)") (class "Default")
      (node (ref "U1") (pin "13") (pinfunction "PA08(I2C/AIN16/SER0:0+)_13") (pintype "bidirectional"))
    )
    (net (code "115") (name "unconnected-(U1-PA09(I2C{slash}AIN17{slash}SER0:1+)-Pad14)") (class "Default")
      (node (ref "U1") (pin "14") (pinfunction "PA09(I2C/AIN17/SER0:1+)_14") (pintype "bidirectional"))
    )
    (net (code "116") (name "unconnected-(U1-PA10(AIN18{slash}SER0:2+)-Pad15)") (class "Default")
      (node (ref "U1") (pin "15") (pinfunction "PA10(AIN18/SER0:2+)_15") (pintype "bidirectional"))
    )
    (net (code "117") (name "unconnected-(U1-PA11(AIN19{slash}SER0:3+)-Pad16)") (class "Default")
      (node (ref "U1") (pin "16") (pinfunction "PA11(AIN19/SER0:3+)_16") (pintype "bidirectional"))
    )
    (net (code "118") (name "unconnected-(U1-PA12(I2C{slash}SER2:0+)-Pad21)") (class "Default")
      (node (ref "U1") (pin "21") (pinfunction "PA12(I2C/SER2:0+)_21") (pintype "bidirectional"))
    )
    (net (code "119") (name "unconnected-(U1-PA13(I2C{slash}SER2:1+)-Pad22)") (class "Default")
      (node (ref "U1") (pin "22") (pinfunction "PA13(I2C/SER2:1+)_22") (pintype "bidirectional"))
    )
    (net (code "120") (name "unconnected-(U1-PA14(XIN{slash}SER2:2+)-Pad23)") (class "Default")
      (node (ref "U1") (pin "23") (pinfunction "PA14(XIN/SER2:2+)_23") (pintype "bidirectional"))
    )
    (net (code "121") (name "unconnected-(U1-PA15(XOUT{slash}SER2:3+)-Pad24)") (class "Default")
      (node (ref "U1") (pin "24") (pinfunction "PA15(XOUT/SER2:3+)_24") (pintype "bidirectional"))
    )
    (net (code "122") (name "unconnected-(U1-PA16(I2C{slash}SER1:0+)-Pad25)") (class "Default")
      (node (ref "U1") (pin "25") (pinfunction "PA16(I2C/SER1:0+)_25") (pintype "bidirectional"))
    )
    (net (code "123") (name "unconnected-(U1-PA17(I2C{slash}SER1:1+)-Pad26)") (class "Default")
      (node (ref "U1") (pin "26") (pinfunction "PA17(I2C/SER1:1+)_26") (pintype "bidirectional"))
    )
    (net (code "124") (name "unconnected-(U1-PA18(SER1:2+)-Pad27)") (class "Default")
      (node (ref "U1") (pin "27") (pinfunction "PA18(SER1:2+)_27") (pintype "bidirectional"))
    )
    (net (code "125") (name "unconnected-(U1-PA19(SER1:3+)-Pad28)") (class "Default")
      (node (ref "U1") (pin "28") (pinfunction "PA19(SER1:3+)_28") (pintype "bidirectional"))
    )
    (net (code "126") (name "unconnected-(U1-PA20(SER5:2+)-Pad29)") (class "Default")
      (node (ref "U1") (pin "29") (pinfunction "PA20(SER5:2+)_29") (pintype "bidirectional"))
    )
    (net (code "127") (name "unconnected-(U1-PA21(SER5:3+)-Pad30)") (class "Default")
      (node (ref "U1") (pin "30") (pinfunction "PA21(SER5:3+)_30") (pintype "bidirectional"))
    )
    (net (code "128") (name "unconnected-(U1-PA22(I2C{slash}SER3:0+)-Pad31)") (class "Default")
      (node (ref "U1") (pin "31") (pinfunction "PA22(I2C/SER3:0+)_31") (pintype "bidirectional"))
    )
    (net (code "129") (name "unconnected-(U1-PA23(I2C{slash}SER3:0+)-Pad32)") (class "Default")
      (node (ref "U1") (pin "32") (pinfunction "PA23(I2C/SER3:0+)_32") (pintype "bidirectional"))
    )
    (net (code "130") (name "unconnected-(U1-PA24(SER3:2+)-Pad33)") (class "Default")
      (node (ref "U1") (pin "33") (pinfunction "PA24(SER3:2+)_33") (pintype "bidirectional"))
    )
    (net (code "131") (name "unconnected-(U1-PA25(SER3:3+)-Pad34)") (class "Default")
      (node (ref "U1") (pin "34") (pinfunction "PA25(SER3:3+)_34") (pintype "bidirectional"))
    )
    (net (code "132") (name "unconnected-(U1-PA27-Pad39)") (class "Default")
      (node (ref "U1") (pin "39") (pinfunction "PA27_39") (pintype "bidirectional"))
    )
    (net (code "133") (name "unconnected-(U1-PA28-Pad41)") (class "Default")
      (node (ref "U1") (pin "41") (pinfunction "PA28_41") (pintype "bidirectional"))
    )
    (net (code "134") (name "unconnected-(U1-PA30(SWCLK{slash}SER1:2+)-Pad45)") (class "Default")
      (node (ref "U1") (pin "45") (pinfunction "PA30(SWCLK/SER1:2+)_45") (pintype "bidirectional"))
    )
    (net (code "135") (name "unconnected-(U1-PA31(SWDIO{slash}SER1:3+)-Pad46)") (class "Default")
      (node (ref "U1") (pin "46") (pinfunction "PA31(SWDIO/SER1:3+)_46") (pintype "bidirectional"))
    )
    (net (code "136") (name "unconnected-(U1-PB02(AIN10{slash}SER5:0)-Pad47)") (class "Default")
      (node (ref "U1") (pin "47") (pinfunction "PB02(AIN10/SER5:0)_47") (pintype "bidirectional"))
    )
    (net (code "137") (name "unconnected-(U1-PB03(AIN11{slash}SER5:1)-Pad48)") (class "Default")
      (node (ref "U1") (pin "48") (pinfunction "PB03(AIN11/SER5:1)_48") (pintype "bidirectional"))
    )
    (net (code "138") (name "unconnected-(U1-PB08(AIN2{slash}SER4:0{slash}TC4:0)-Pad7)") (class "Default")
      (node (ref "U1") (pin "7") (pinfunction "PB08(AIN2/SER4:0/TC4:0)_7") (pintype "bidirectional"))
    )
    (net (code "139") (name "unconnected-(U1-PB09(AIN3{slash}SER4:1{slash}TC4:1)-Pad8)") (class "Default")
      (node (ref "U1") (pin "8") (pinfunction "PB09(AIN3/SER4:1/TC4:1)_8") (pintype "bidirectional"))
    )
    (net (code "140") (name "unconnected-(U1-PB10(SER4:2+)-Pad19)") (class "Default")
      (node (ref "U1") (pin "19") (pinfunction "PB10(SER4:2+)_19") (pintype "bidirectional"))
    )
    (net (code "141") (name "unconnected-(U1-PB11(SER4:3+)-Pad20)") (class "Default")
      (node (ref "U1") (pin "20") (pinfunction "PB11(SER4:3+)_20") (pintype "bidirectional"))
    )
    (net (code "142") (name "unconnected-(U1-PB22(SER5:2+)-Pad37)") (class "Default")
      (node (ref "U1") (pin "37") (pinfunction "PB22(SER5:2+)_37") (pintype "bidirectional"))
    )
    (net (code "143") (name "unconnected-(U1-PB23(SER5:3+)-Pad38)") (class "Default")
      (node (ref "U1") (pin "38") (pinfunction "PB23(SER5:3+)_38") (pintype "bidirectional"))
    )
    (net (code "144") (name "unconnected-(U1-VDDANA-Pad6)") (class "Default")
      (node (ref "U1") (pin "6") (pinfunction "VDDANA_6") (pintype "bidirectional"))
    )
    (net (code "145") (name "unconnected-(U1-VDDCORE-Pad43)") (class "Default")
      (node (ref "U1") (pin "43") (pinfunction "VDDCORE_43") (pintype "bidirectional"))
    )
    (net (code "146") (name "unconnected-(U1-VDDIN-Pad44)") (class "Default")
      (node (ref "U1") (pin "44") (pinfunction "VDDIN_44") (pintype "bidirectional"))
    )
    (net (code "147") (name "unconnected-(U1-VDDIO-Pad17)") (class "Default")
      (node (ref "U1") (pin "17") (pinfunction "VDDIO_17") (pintype "bidirectional"))
    )
    (net (code "148") (name "unconnected-(U1-VDDIO-Pad36)") (class "Default")
      (node (ref "U1") (pin "36") (pinfunction "VDDIO_36") (pintype "bidirectional"))
    )
    (net (code "149") (name "unconnected-(U1-~{RESET}-Pad40)") (class "Default")
      (node (ref "U1") (pin "40") (pinfunction "~{RESET}_40") (pintype "bidirectional"))
    )
    (net (code "150") (name "unconnected-(U6-R2IN-Pad8)") (class "Default")
      (node (ref "U6") (pin "8") (pinfunction "R2IN_8") (pintype "input"))
    )
    (net (code "151") (name "unconnected-(U6-R2OUT-Pad9)") (class "Default")
      (node (ref "U6") (pin "9") (pinfunction "R2OUT_9") (pintype "output"))
    )
    (net (code "152") (name "unconnected-(U6-T2IN-Pad10)") (class "Default")
      (node (ref "U6") (pin "10") (pinfunction "T2IN_10") (pintype "input"))
    )
    (net (code "153") (name "unconnected-(U6-T2OUT-Pad7)") (class "Default")
      (node (ref "U6") (pin "7") (pinfunction "T2OUT_7") (pintype "output"))
    )
  )
)
